# HMC326.net
KiCad netlist of a schematic drawn in Altium Designer
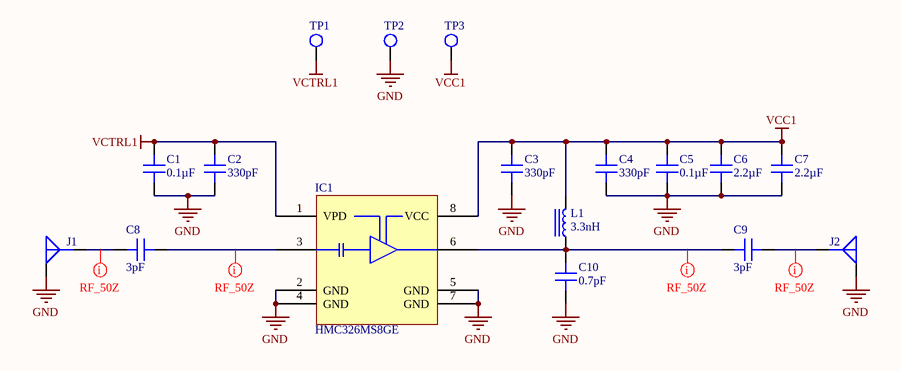
[diagram p0: HMC326.SchDoc]

(export (version "E")
  (design (tool "Eeschema 10.0.6"))
  (components
    (comp (ref "C1")
      (value "0.1µF")
      (footprint "CAP 0402_1005")
      (description "CAP CER 0.1UF 16V X7R 0402")
      (fields (field (name "PART NUMBER") "EMK105B7104KV-F") (field (name "MANUFACTURER") "Taiyo Yuden"))
      (libsource (lib "Celestial Altium Library - altium_library") (part "Capacitor"))
    )
    (comp (ref "C2")
      (value "330pF")
      (footprint "CAP 0402_1005")
      (description "CAP CER 330PF 50V X7R 0402")
      (fields
        (field (name "PART NUMBER") "CL05B331KB5NNNC")
        (field (name "MANUFACTURER") "Samsung Electro-Mechanics")
      )
      (libsource (lib "Celestial Altium Library - altium_library") (part "Capacitor"))
    )
    (comp (ref "C3")
      (value "330pF")
      (footprint "CAP 0402_1005")
      (description "CAP CER 330PF 50V X7R 0402")
      (fields
        (field (name "PART NUMBER") "CL05B331KB5NNNC")
        (field (name "MANUFACTURER") "Samsung Electro-Mechanics")
      )
      (libsource (lib "Celestial Altium Library - altium_library") (part "Capacitor"))
    )
    (comp (ref "C4")
      (value "330pF")
      (footprint "CAP 0402_1005")
      (description "CAP CER 330PF 50V X7R 0402")
      (fields
        (field (name "PART NUMBER") "CL05B331KB5NNNC")
        (field (name "MANUFACTURER") "Samsung Electro-Mechanics")
      )
      (libsource (lib "Celestial Altium Library - altium_library") (part "Capacitor"))
    )
    (comp (ref "C5")
      (value "0.1µF")
      (footprint "CAP 0402_1005")
      (description "CAP CER 0.1UF 16V X7R 0402")
      (fields (field (name "PART NUMBER") "EMK105B7104KV-F") (field (name "MANUFACTURER") "Taiyo Yuden"))
      (libsource (lib "Celestial Altium Library - altium_library") (part "Capacitor"))
    )
    (comp (ref "C6")
      (value "2.2µF")
      (footprint "CAP 0402_1005")
      (description "CAP CER 2.2UF 10V X5R 0402")
      (fields (field (name "PART NUMBER") "LMK105BJ225MV-F") (field (name "MANUFACTURER") "Taiyo Yuden"))
      (libsource (lib "Celestial Altium Library - altium_library") (part "Capacitor"))
    )
    (comp (ref "C7")
      (value "2.2µF")
      (footprint "CAP 0402_1005")
      (description "CAP CER 2.2UF 10V X5R 0402")
      (fields (field (name "PART NUMBER") "LMK105BJ225MV-F") (field (name "MANUFACTURER") "Taiyo Yuden"))
      (libsource (lib "Celestial Altium Library - altium_library") (part "Capacitor"))
    )
    (comp (ref "C8")
      (value "3pF")
      (footprint "CAP 0402_1005 RF")
      (description "CAP CER 3PF 50V C0G/NP0 0402")
      (fields
        (field (name "PART NUMBER") "GJM1555C1H3R0CB01J")
        (field (name "MANUFACTURER") "Murata Electronics")
      )
      (libsource (lib "Celestial Altium Library - altium_library") (part "Capacitor"))
    )
    (comp (ref "C9")
      (value "3pF")
      (footprint "CAP 0402_1005 RF")
      (description "CAP CER 3PF 50V C0G/NP0 0402")
      (fields
        (field (name "PART NUMBER") "GJM1555C1H3R0CB01J")
        (field (name "MANUFACTURER") "Murata Electronics")
      )
      (libsource (lib "Celestial Altium Library - altium_library") (part "Capacitor"))
    )
    (comp (ref "C10")
      (value "0.7pF")
      (footprint "CAP 0402_1005 RF")
      (description "CAP CER 0.7PF 50V C0G/NP0 0402")
      (fields
        (field (name "PART NUMBER") "GJM1555C1HR70BB01D")
        (field (name "MANUFACTURER") "Murata Electronics")
      )
      (libsource (lib "Celestial Altium Library - altium_library") (part "Capacitor"))
    )
    (comp (ref "IC1")
      (value "HMC326MS8GE")
      (footprint "ANALOG MSOP8G 3x3MM")
      (description "IC RF AMP GP 3GHZ-4.5GHZ 8MSOP")
      (libsource (lib "IC") (part "HMC326MS8GE"))
    )
    (comp (ref "J1")
      (value "CON-SMA-EDGE-S")
      (footprint "CON-SMA-EDGE-S")
      (description "CONN SMA JACK STR EDGE MNT")
      (libsource (lib "Connector") (part "CON-SMA-EDGE-S"))
    )
    (comp (ref "J2")
      (value "CON-SMA-EDGE-S")
      (footprint "CON-SMA-EDGE-S")
      (description "CONN SMA JACK STR EDGE MNT")
      (libsource (lib "Connector") (part "CON-SMA-EDGE-S"))
    )
    (comp (ref "L1")
      (value "3.3nH")
      (footprint "0603HP")
      (description "Fixed Inductors 0603 3.3nH Unshld 2% 1.9A 24mOhms")
      (libsource (lib "Inductor") (part "0603HP-3N3XGLW"))
    )
    (comp (ref "TP1")
      (value "Test Point-THM")
      (footprint "KEYSTONE-THM-TestPoint")
      (description "THRU HOLE MOUNT TEST POINTS")
      (libsource (lib "Misc") (part "Test Point-THM"))
    )
    (comp (ref "TP2")
      (value "Test Point-THM")
      (footprint "KEYSTONE-THM-TestPoint")
      (description "THRU HOLE MOUNT TEST POINTS")
      (libsource (lib "Misc") (part "Test Point-THM"))
    )
    (comp (ref "TP3")
      (value "Test Point-THM")
      (footprint "KEYSTONE-THM-TestPoint")
      (description "THRU HOLE MOUNT TEST POINTS")
      (libsource (lib "Misc") (part "Test Point-THM"))
    )
  )
  (nets
    (net (code "1") (name "GND") (class "Default")
      (node (ref "C1") (pin "1") (pinfunction "1_1") (pintype "passive"))
      (node (ref "C10") (pin "1") (pinfunction "1_1") (pintype "passive"))
      (node (ref "C2") (pin "1") (pinfunction "1_1") (pintype "passive"))
      (node (ref "C3") (pin "1") (pinfunction "1_1") (pintype "passive"))
      (node (ref "C4") (pin "1") (pinfunction "1_1") (pintype "passive"))
      (node (ref "C5") (pin "1") (pinfunction "1_1") (pintype "passive"))
      (node (ref "C6") (pin "1") (pinfunction "1_1") (pintype "passive"))
      (node (ref "C7") (pin "1") (pinfunction "1_1") (pintype "passive"))
      (node (ref "IC1") (pin "2") (pinfunction "GND_2") (pintype "passive"))
      (node (ref "IC1") (pin "4") (pinfunction "GND_4") (pintype "passive"))
      (node (ref "IC1") (pin "5") (pinfunction "GND_5") (pintype "passive"))
      (node (ref "IC1") (pin "7") (pinfunction "GND_7") (pintype "passive"))
      (node (ref "J1") (pin "2") (pinfunction "G_2") (pintype "passive"))
      (node (ref "J2") (pin "2") (pinfunction "G_2") (pintype "passive"))
      (node (ref "TP2") (pin "1") (pinfunction "TP_1") (pintype "passive"))
    )
    (net (code "2") (name "Net-(IC1-IN)") (class "Default")
      (node (ref "C8") (pin "1") (pinfunction "1_1") (pintype "passive"))
      (node (ref "IC1") (pin "3") (pinfunction "IN_3") (pintype "passive"))
    )
    (net (code "3") (name "Net-(IC1-OUT)") (class "Default")
      (node (ref "C10") (pin "2") (pinfunction "2_2") (pintype "passive"))
      (node (ref "C9") (pin "1") (pinfunction "1_1") (pintype "passive"))
      (node (ref "IC1") (pin "6") (pinfunction "OUT_6") (pintype "passive"))
      (node (ref "L1") (pin "1") (pinfunction "1_1") (pintype "passive"))
    )
    (net (code "4") (name "Net-(J1-S)") (class "Default")
      (node (ref "C8") (pin "2") (pinfunction "2_2") (pintype "passive"))
      (node (ref "J1") (pin "1") (pinfunction "S_1") (pintype "passive"))
    )
    (net (code "5") (name "Net-(J2-S)") (class "Default")
      (node (ref "C9") (pin "2") (pinfunction "2_2") (pintype "passive"))
      (node (ref "J2") (pin "1") (pinfunction "S_1") (pintype "passive"))
    )
    (net (code "6") (name "VCC1") (class "Default")
      (node (ref "C3") (pin "2") (pinfunction "2_2") (pintype "passive"))
      (node (ref "C4") (pin "2") (pinfunction "2_2") (pintype "passive"))
      (node (ref "C5") (pin "2") (pinfunction "2_2") (pintype "passive"))
      (node (ref "C6") (pin "2") (pinfunction "2_2") (pintype "passive"))
      (node (ref "C7") (pin "2") (pinfunction "2_2") (pintype "passive"))
      (node (ref "IC1") (pin "8") (pinfunction "VCC_8") (pintype "passive"))
      (node (ref "L1") (pin "2") (pinfunction "2_2") (pintype "passive"))
      (node (ref "TP3") (pin "1") (pinfunction "TP_1") (pintype "passive"))
    )
    (net (code "7") (name "VCTRL1") (class "Default")
      (node (ref "C1") (pin "2") (pinfunction "2_2") (pintype "passive"))
      (node (ref "C2") (pin "2") (pinfunction "2_2") (pintype "passive"))
      (node (ref "IC1") (pin "1") (pinfunction "VPD_1") (pintype "passive"))
      (node (ref "TP1") (pin "1") (pinfunction "TP_1") (pintype "passive"))
    )
  )
)
